# SmartLink.net
KiCad netlist of a schematic drawn in Altium Designer
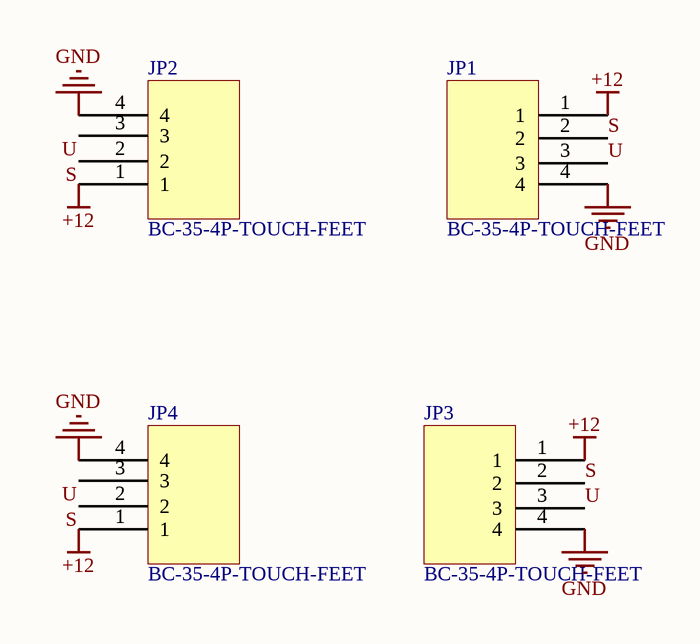
[diagram p0: SmartLink.SchDoc]

(export (version "E")
  (design (tool "Eeschema 10.0.6"))
  (components
    (comp (ref "JP1")
      (value "BC-35-4P-TOUCH-FEET")
      (footprint "BC-35-4P-TOUCH-FEET")
      (libsource (lib "") (part "BC-35-4P-TOUCH-FEET_1"))
    )
    (comp (ref "JP2")
      (value "BC-35-4P-TOUCH-FEET")
      (footprint "BC-35-4P-TOUCH-FEET")
      (libsource (lib "15.1 - 未分类器件") (part "BC-35-4P-TOUCH-FEET"))
    )
    (comp (ref "JP3")
      (value "BC-35-4P-TOUCH-FEET")
      (footprint "BC-35-4P-TOUCH-FEET")
      (libsource (lib "") (part "BC-35-4P-TOUCH-FEET_1"))
    )
    (comp (ref "JP4")
      (value "BC-35-4P-TOUCH-FEET")
      (footprint "BC-35-4P-TOUCH-FEET")
      (libsource (lib "15.1 - 未分类器件") (part "BC-35-4P-TOUCH-FEET"))
    )
  )
  (nets
    (net (code "1") (name "+12") (class "Default")
      (node (ref "JP1") (pin "1") (pinfunction "1_1") (pintype "passive"))
      (node (ref "JP2") (pin "1") (pinfunction "1_1") (pintype "passive"))
      (node (ref "JP3") (pin "1") (pinfunction "1_1") (pintype "passive"))
      (node (ref "JP4") (pin "1") (pinfunction "1_1") (pintype "passive"))
    )
    (net (code "2") (name "/S") (class "Default")
      (node (ref "JP1") (pin "2") (pinfunction "2_2") (pintype "passive"))
      (node (ref "JP2") (pin "2") (pinfunction "2_2") (pintype "passive"))
      (node (ref "JP3") (pin "2") (pinfunction "2_2") (pintype "passive"))
      (node (ref "JP4") (pin "2") (pinfunction "2_2") (pintype "passive"))
    )
    (net (code "3") (name "/U") (class "Default")
      (node (ref "JP1") (pin "3") (pinfunction "3_3") (pintype "passive"))
      (node (ref "JP2") (pin "3") (pinfunction "3_3") (pintype "passive"))
      (node (ref "JP3") (pin "3") (pinfunction "3_3") (pintype "passive"))
      (node (ref "JP4") (pin "3") (pinfunction "3_3") (pintype "passive"))
    )
    (net (code "4") (name "GND") (class "Default")
      (node (ref "JP1") (pin "4") (pinfunction "4_4") (pintype "passive"))
      (node (ref "JP2") (pin "4") (pinfunction "4_4") (pintype "passive"))
      (node (ref "JP3") (pin "4") (pinfunction "4_4") (pintype "passive"))
      (node (ref "JP4") (pin "4") (pinfunction "4_4") (pintype "passive"))
    )
  )
)
